# untitled.net
KiCad netlist of a schematic drawn in EAGLE
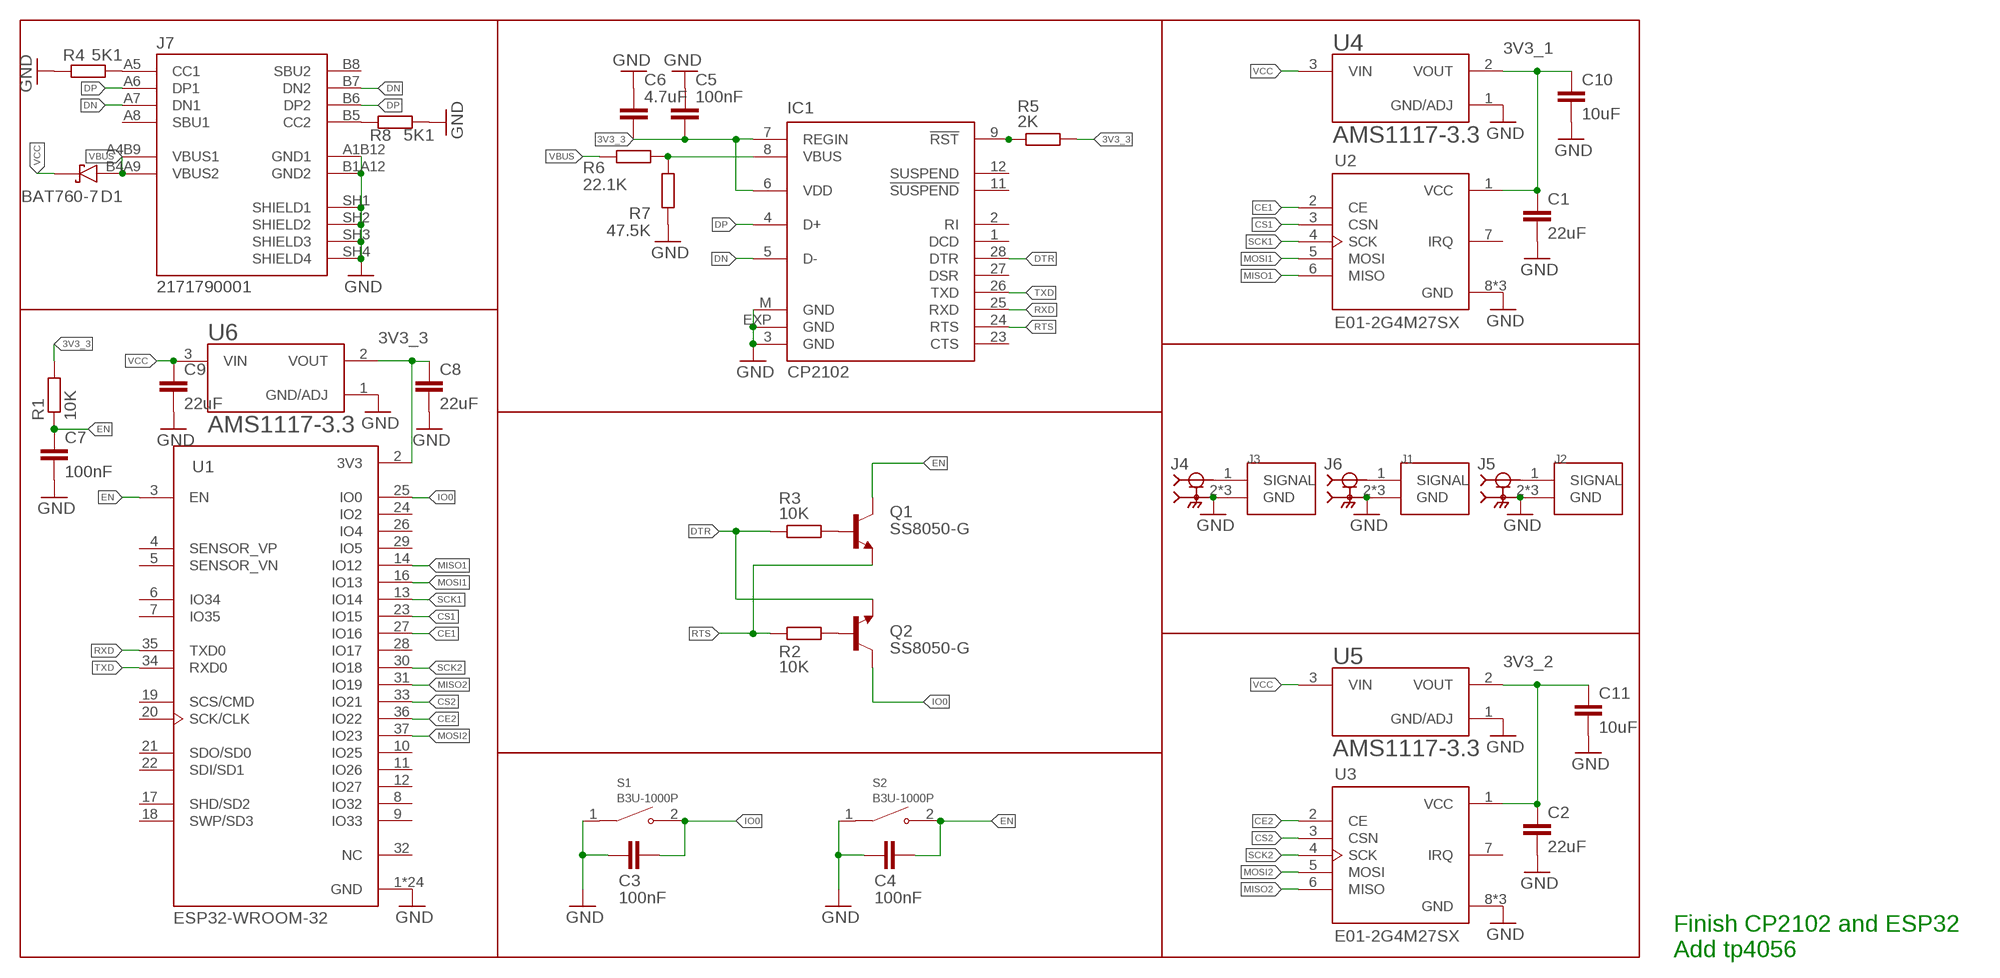
[diagram p0: schematic, sheet 1]

(export (version "E")
  (design (tool "Eeschema 10.0.6"))
  (components
    (comp (ref "C1")
      (value "22uF")
      (footprint "eagle-import:C0603")
      (libsource (lib "eagle-import") (part "C-EUC0603"))
    )
    (comp (ref "C2")
      (value "22uF")
      (footprint "eagle-import:C0603")
      (libsource (lib "eagle-import") (part "C-EUC0603"))
    )
    (comp (ref "C3")
      (value "100nF")
      (footprint "eagle-import:C0603")
      (libsource (lib "eagle-import") (part "C-EUC0603"))
    )
    (comp (ref "C4")
      (value "100nF")
      (footprint "eagle-import:C0603")
      (libsource (lib "eagle-import") (part "C-EUC0603"))
    )
    (comp (ref "C5")
      (value "100nF")
      (footprint "eagle-import:C0603")
      (libsource (lib "eagle-import") (part "C-EUC0603"))
    )
    (comp (ref "C6")
      (value "4.7uF")
      (footprint "eagle-import:C0603")
      (libsource (lib "eagle-import") (part "C-EUC0603"))
    )
    (comp (ref "C7")
      (value "100nF")
      (footprint "eagle-import:C0603")
      (libsource (lib "eagle-import") (part "C-EUC0603"))
    )
    (comp (ref "C8")
      (value "22uF")
      (footprint "eagle-import:C0603")
      (libsource (lib "eagle-import") (part "C-EUC0603"))
    )
    (comp (ref "C9")
      (value "22uF")
      (footprint "eagle-import:C0603")
      (libsource (lib "eagle-import") (part "C-EUC0603"))
    )
    (comp (ref "C10")
      (value "10uF")
      (footprint "eagle-import:C0603")
      (libsource (lib "eagle-import") (part "C-EUC0603"))
    )
    (comp (ref "C11")
      (value "10uF")
      (footprint "eagle-import:C0603")
      (libsource (lib "eagle-import") (part "C-EUC0603"))
    )
    (comp (ref "D1")
      (value "BAT760-7")
      (footprint "eagle-import:SOD2513X120N")
      (fields (field (name "MF") "Diodes Inc."))
      (libsource (lib "eagle-import") (part "BAT760-7"))
    )
    (comp (ref "IC1")
      (value "CP2102")
      (footprint "eagle-import:MLP28")
      (fields (field (name "MF") "FARNELL") (field (name "MPN") "CP2102-GM"))
      (libsource (lib "eagle-import") (part "CP2102"))
    )
    (comp (ref "J1")
      (value "RSP-122811-02")
      (footprint "eagle-import:SAMTEC_RSP-122811-02")
      (fields (field (name "MF") "Samtec Inc."))
      (libsource (lib "eagle-import") (part "RSP-122811-02"))
    )
    (comp (ref "J2")
      (value "RSP-122811-02")
      (footprint "eagle-import:SAMTEC_RSP-122811-02")
      (fields (field (name "MF") "Samtec Inc."))
      (libsource (lib "eagle-import") (part "RSP-122811-02"))
    )
    (comp (ref "J3")
      (value "RSP-122811-02")
      (footprint "eagle-import:SAMTEC_RSP-122811-02")
      (fields (field (name "MF") "Samtec Inc."))
      (libsource (lib "eagle-import") (part "RSP-122811-02"))
    )
    (comp (ref "J4")
      (value "SMA-J-P-X-RA-TH1")
      (footprint "eagle-import:SAMTEC_SMA-J-P-X-RA-TH1")
      (fields (field (name "MF") "Samtec") (field (name "MP") "SMA-J-P-H-RA-TH1"))
      (libsource (lib "eagle-import") (part "SMA-J-P-X-RA-TH1"))
    )
    (comp (ref "J5")
      (value "SMA-J-P-X-RA-TH1")
      (footprint "eagle-import:SAMTEC_SMA-J-P-X-RA-TH1")
      (fields (field (name "MF") "Samtec") (field (name "MP") "SMA-J-P-H-RA-TH1"))
      (libsource (lib "eagle-import") (part "SMA-J-P-X-RA-TH1"))
    )
    (comp (ref "J6")
      (value "SMA-J-P-X-RA-TH1")
      (footprint "eagle-import:SAMTEC_SMA-J-P-X-RA-TH1")
      (fields (field (name "MF") "Samtec") (field (name "MP") "SMA-J-P-H-RA-TH1"))
      (libsource (lib "eagle-import") (part "SMA-J-P-X-RA-TH1"))
    )
    (comp (ref "J7")
      (value "2171790001")
      (footprint "eagle-import:MOLEX_2171790001")
      (fields (field (name "MF") "Molex") (field (name "MP") "217179-0001"))
      (libsource (lib "eagle-import") (part "2171790001"))
    )
    (comp (ref "Q1")
      (value "SS8050-G")
      (footprint "eagle-import:TRANS_SS8050-G")
      (fields (field (name "MF") "Comchip Technology"))
      (libsource (lib "eagle-import") (part "SS8050-G"))
    )
    (comp (ref "Q2")
      (value "SS8050-G")
      (footprint "eagle-import:TRANS_SS8050-G")
      (fields (field (name "MF") "Comchip Technology"))
      (libsource (lib "eagle-import") (part "SS8050-G"))
    )
    (comp (ref "R1")
      (value "10K")
      (footprint "eagle-import:R0603")
      (libsource (lib "eagle-import") (part "R-EU_R0603"))
    )
    (comp (ref "R2")
      (value "10K")
      (footprint "eagle-import:R0603")
      (libsource (lib "eagle-import") (part "R-EU_R0603"))
    )
    (comp (ref "R3")
      (value "10K")
      (footprint "eagle-import:R0603")
      (libsource (lib "eagle-import") (part "R-EU_R0603"))
    )
    (comp (ref "R4")
      (value "5K1")
      (footprint "eagle-import:R0603")
      (libsource (lib "eagle-import") (part "R-EU_R0603"))
    )
    (comp (ref "R5")
      (value "2K")
      (footprint "eagle-import:R0603")
      (libsource (lib "eagle-import") (part "R-EU_R0603"))
    )
    (comp (ref "R6")
      (value "22.1K")
      (footprint "eagle-import:R0603")
      (libsource (lib "eagle-import") (part "R-EU_R0603"))
    )
    (comp (ref "R7")
      (value "47.5K")
      (footprint "eagle-import:R0603")
      (libsource (lib "eagle-import") (part "R-EU_R0603"))
    )
    (comp (ref "R8")
      (value "5K1")
      (footprint "eagle-import:R0603")
      (libsource (lib "eagle-import") (part "R-EU_R0603"))
    )
    (comp (ref "S1")
      (value "B3U-1000P")
      (footprint "eagle-import:SW_B3U-1000P")
      (fields (field (name "MF") "Omron"))
      (libsource (lib "eagle-import") (part "B3U-1000P"))
    )
    (comp (ref "S2")
      (value "B3U-1000P")
      (footprint "eagle-import:SW_B3U-1000P")
      (fields (field (name "MF") "Omron"))
      (libsource (lib "eagle-import") (part "B3U-1000P"))
    )
    (comp (ref "U1")
      (value "ESP32-WROOM-32")
      (footprint "eagle-import:MODULE_ESP32-WROOM-32")
      (fields (field (name "MF") "Espressif Systems"))
      (libsource (lib "eagle-import") (part "ESP32-WROOM-32"))
    )
    (comp (ref "U2")
      (value "E01-2G4M27SX")
      (footprint "eagle-import:XCVR_E01-2G4M27SX")
      (fields (field (name "MF") "EBYTE"))
      (libsource (lib "eagle-import") (part "E01-2G4M27SX"))
    )
    (comp (ref "U3")
      (value "E01-2G4M27SX")
      (footprint "eagle-import:XCVR_E01-2G4M27SX")
      (fields (field (name "MF") "EBYTE"))
      (libsource (lib "eagle-import") (part "E01-2G4M27SX"))
    )
    (comp (ref "U4")
      (value "AMS1117-3.3")
      (footprint "eagle-import:SOT229P700X180-4N")
      (fields (field (name "MF") "Advanced Monolithic Systems"))
      (libsource (lib "eagle-import") (part "AMS1117-3.3"))
    )
    (comp (ref "U5")
      (value "AMS1117-3.3")
      (footprint "eagle-import:SOT229P700X180-4N")
      (fields (field (name "MF") "Advanced Monolithic Systems"))
      (libsource (lib "eagle-import") (part "AMS1117-3.3"))
    )
    (comp (ref "U6")
      (value "AMS1117-3.3")
      (footprint "eagle-import:SOT229P700X180-4N")
      (fields (field (name "MF") "Advanced Monolithic Systems"))
      (libsource (lib "eagle-import") (part "AMS1117-3.3"))
    )
  )
  (nets
    (net (code "1") (name "/3V3_1") (class "Default")
      (node (ref "C1") (pin "1") (pinfunction "1_1") (pintype "passive"))
      (node (ref "C10") (pin "1") (pinfunction "1_1") (pintype "passive"))
      (node (ref "U2") (pin "1") (pinfunction "VCC_1") (pintype "power_in"))
      (node (ref "U4") (pin "2") (pinfunction "VOUT_2") (pintype "output"))
    )
    (net (code "2") (name "/3V3_2") (class "Default")
      (node (ref "C11") (pin "1") (pinfunction "1_1") (pintype "passive"))
      (node (ref "C2") (pin "1") (pinfunction "1_1") (pintype "passive"))
      (node (ref "U3") (pin "1") (pinfunction "VCC_1") (pintype "power_in"))
      (node (ref "U5") (pin "2") (pinfunction "VOUT_2") (pintype "output"))
    )
    (net (code "3") (name "3V3_3") (class "Default")
      (node (ref "C5") (pin "2") (pinfunction "2_2") (pintype "passive"))
      (node (ref "C6") (pin "2") (pinfunction "2_2") (pintype "passive"))
      (node (ref "C8") (pin "1") (pinfunction "1_1") (pintype "passive"))
      (node (ref "IC1") (pin "6") (pinfunction "VDD_6") (pintype "power_in"))
      (node (ref "IC1") (pin "7") (pinfunction "REGIN_7") (pintype "passive"))
      (node (ref "R1") (pin "2") (pinfunction "2_2") (pintype "passive"))
      (node (ref "R5") (pin "2") (pinfunction "2_2") (pintype "passive"))
      (node (ref "U1") (pin "2") (pinfunction "3V3_2") (pintype "power_in"))
      (node (ref "U6") (pin "2") (pinfunction "VOUT_2") (pintype "output"))
    )
    (net (code "4") (name "CE1") (class "Default")
      (node (ref "U1") (pin "27") (pinfunction "IO16_27") (pintype "bidirectional"))
      (node (ref "U2") (pin "2") (pinfunction "CE_2") (pintype "input"))
    )
    (net (code "5") (name "CE2") (class "Default")
      (node (ref "U1") (pin "36") (pinfunction "IO22_36") (pintype "bidirectional"))
      (node (ref "U3") (pin "2") (pinfunction "CE_2") (pintype "input"))
    )
    (net (code "6") (name "CS1") (class "Default")
      (node (ref "U1") (pin "23") (pinfunction "IO15_23") (pintype "bidirectional"))
      (node (ref "U2") (pin "3") (pinfunction "CSN_3") (pintype "input"))
    )
    (net (code "7") (name "CS2") (class "Default")
      (node (ref "U1") (pin "33") (pinfunction "IO21_33") (pintype "bidirectional"))
      (node (ref "U3") (pin "3") (pinfunction "CSN_3") (pintype "input"))
    )
    (net (code "8") (name "DN") (class "Default")
      (node (ref "IC1") (pin "5") (pinfunction "D-_5") (pintype "bidirectional"))
      (node (ref "J7") (pin "A7") (pinfunction "DN1_A7") (pintype "bidirectional"))
      (node (ref "J7") (pin "B7") (pinfunction "DN2_B7") (pintype "bidirectional"))
    )
    (net (code "9") (name "DP") (class "Default")
      (node (ref "IC1") (pin "4") (pinfunction "D+_4") (pintype "bidirectional"))
      (node (ref "J7") (pin "A6") (pinfunction "DP1_A6") (pintype "bidirectional"))
      (node (ref "J7") (pin "B6") (pinfunction "DP2_B6") (pintype "bidirectional"))
    )
    (net (code "10") (name "DTR") (class "Default")
      (node (ref "IC1") (pin "28") (pinfunction "DTR_28") (pintype "output"))
      (node (ref "Q2") (pin "2") (pinfunction "E_2") (pintype "passive"))
      (node (ref "R3") (pin "1") (pinfunction "1_1") (pintype "passive"))
    )
    (net (code "11") (name "EN") (class "Default")
      (node (ref "C4") (pin "2") (pinfunction "2_2") (pintype "passive"))
      (node (ref "C7") (pin "1") (pinfunction "1_1") (pintype "passive"))
      (node (ref "Q1") (pin "3") (pinfunction "C_3") (pintype "passive"))
      (node (ref "R1") (pin "1") (pinfunction "1_1") (pintype "passive"))
      (node (ref "S2") (pin "2") (pinfunction "2_2") (pintype "passive"))
      (node (ref "U1") (pin "3") (pinfunction "EN_3") (pintype "input"))
    )
    (net (code "12") (name "GND") (class "Default")
      (node (ref "C1") (pin "2") (pinfunction "2_2") (pintype "passive"))
      (node (ref "C10") (pin "2") (pinfunction "2_2") (pintype "passive"))
      (node (ref "C11") (pin "2") (pinfunction "2_2") (pintype "passive"))
      (node (ref "C2") (pin "2") (pinfunction "2_2") (pintype "passive"))
      (node (ref "C3") (pin "1") (pinfunction "1_1") (pintype "passive"))
      (node (ref "C4") (pin "1") (pinfunction "1_1") (pintype "passive"))
      (node (ref "C5") (pin "1") (pinfunction "1_1") (pintype "passive"))
      (node (ref "C6") (pin "1") (pinfunction "1_1") (pintype "passive"))
      (node (ref "C7") (pin "2") (pinfunction "2_2") (pintype "passive"))
      (node (ref "C8") (pin "2") (pinfunction "2_2") (pintype "passive"))
      (node (ref "C9") (pin "2") (pinfunction "2_2") (pintype "passive"))
      (node (ref "IC1") (pin "3") (pinfunction "GND_3") (pintype "power_in"))
      (node (ref "IC1") (pin "EXP") (pinfunction "GND_EXP") (pintype "power_in"))
      (node (ref "IC1") (pin "M") (pinfunction "GND_M") (pintype "power_in"))
      (node (ref "J1") (pin "2") (pinfunction "GND_2") (pintype "power_in"))
      (node (ref "J1") (pin "3") (pinfunction "GND_3") (pintype "power_in"))
      (node (ref "J1") (pin "4") (pinfunction "GND_4") (pintype "power_in"))
      (node (ref "J2") (pin "2") (pinfunction "GND_2") (pintype "power_in"))
      (node (ref "J2") (pin "3") (pinfunction "GND_3") (pintype "power_in"))
      (node (ref "J2") (pin "4") (pinfunction "GND_4") (pintype "power_in"))
      (node (ref "J3") (pin "2") (pinfunction "GND_2") (pintype "power_in"))
      (node (ref "J3") (pin "3") (pinfunction "GND_3") (pintype "power_in"))
      (node (ref "J3") (pin "4") (pinfunction "GND_4") (pintype "power_in"))
      (node (ref "J4") (pin "2") (pinfunction "2_2") (pintype "passive"))
      (node (ref "J4") (pin "3") (pinfunction "2_3") (pintype "passive"))
      (node (ref "J4") (pin "4") (pinfunction "2_4") (pintype "passive"))
      (node (ref "J4") (pin "5") (pinfunction "2_5") (pintype "passive"))
      (node (ref "J5") (pin "2") (pinfunction "2_2") (pintype "passive"))
      (node (ref "J5") (pin "3") (pinfunction "2_3") (pintype "passive"))
      (node (ref "J5") (pin "4") (pinfunction "2_4") (pintype "passive"))
      (node (ref "J5") (pin "5") (pinfunction "2_5") (pintype "passive"))
      (node (ref "J6") (pin "2") (pinfunction "2_2") (pintype "passive"))
      (node (ref "J6") (pin "3") (pinfunction "2_3") (pintype "passive"))
      (node (ref "J6") (pin "4") (pinfunction "2_4") (pintype "passive"))
      (node (ref "J6") (pin "5") (pinfunction "2_5") (pintype "passive"))
      (node (ref "J7") (pin "A1B12") (pinfunction "GND1_A1B12") (pintype "power_in"))
      (node (ref "J7") (pin "B1A12") (pinfunction "GND2_B1A12") (pintype "power_in"))
      (node (ref "J7") (pin "SH1") (pinfunction "SHIELD1_SH1") (pintype "passive"))
      (node (ref "J7") (pin "SH2") (pinfunction "SHIELD2_SH2") (pintype "passive"))
      (node (ref "J7") (pin "SH3") (pinfunction "SHIELD3_SH3") (pintype "passive"))
      (node (ref "J7") (pin "SH4") (pinfunction "SHIELD4_SH4") (pintype "passive"))
      (node (ref "R4") (pin "1") (pinfunction "1_1") (pintype "passive"))
      (node (ref "R7") (pin "1") (pinfunction "1_1") (pintype "passive"))
      (node (ref "R8") (pin "2") (pinfunction "2_2") (pintype "passive"))
      (node (ref "S1") (pin "1") (pinfunction "1_1") (pintype "passive"))
      (node (ref "S2") (pin "1") (pinfunction "1_1") (pintype "passive"))
      (node (ref "U1") (pin "1") (pinfunction "GND_1") (pintype "power_in"))
      (node (ref "U1") (pin "15") (pinfunction "GND_15") (pintype "power_in"))
      (node (ref "U1") (pin "38") (pinfunction "GND_38") (pintype "power_in"))
      (node (ref "U1") (pin "39_1") (pinfunction "GND_39_1") (pintype "power_in"))
      (node (ref "U1") (pin "39_10") (pinfunction "GND_39_10") (pintype "power_in"))
      (node (ref "U1") (pin "39_11") (pinfunction "GND_39_11") (pintype "power_in"))
      (node (ref "U1") (pin "39_12") (pinfunction "GND_39_12") (pintype "power_in"))
      (node (ref "U1") (pin "39_13") (pinfunction "GND_39_13") (pintype "power_in"))
      (node (ref "U1") (pin "39_14") (pinfunction "GND_39_14") (pintype "power_in"))
      (node (ref "U1") (pin "39_15") (pinfunction "GND_39_15") (pintype "power_in"))
      (node (ref "U1") (pin "39_16") (pinfunction "GND_39_16") (pintype "power_in"))
      (node (ref "U1") (pin "39_17") (pinfunction "GND_39_17") (pintype "power_in"))
      (node (ref "U1") (pin "39_18") (pinfunction "GND_39_18") (pintype "power_in"))
      (node (ref "U1") (pin "39_19") (pinfunction "GND_39_19") (pintype "power_in"))
      (node (ref "U1") (pin "39_2") (pinfunction "GND_39_2") (pintype "power_in"))
      (node (ref "U1") (pin "39_20") (pinfunction "GND_39_20") (pintype "power_in"))
      (node (ref "U1") (pin "39_21") (pinfunction "GND_39_21") (pintype "power_in"))
      (node (ref "U1") (pin "39_3") (pinfunction "GND_39_3") (pintype "power_in"))
      (node (ref "U1") (pin "39_4") (pinfunction "GND_39_4") (pintype "power_in"))
      (node (ref "U1") (pin "39_5") (pinfunction "GND_39_5") (pintype "power_in"))
      (node (ref "U1") (pin "39_6") (pinfunction "GND_39_6") (pintype "power_in"))
      (node (ref "U1") (pin "39_7") (pinfunction "GND_39_7") (pintype "power_in"))
      (node (ref "U1") (pin "39_8") (pinfunction "GND_39_8") (pintype "power_in"))
      (node (ref "U1") (pin "39_9") (pinfunction "GND_39_9") (pintype "power_in"))
      (node (ref "U2") (pin "10") (pinfunction "GND_10") (pintype "power_in"))
      (node (ref "U2") (pin "8") (pinfunction "GND_8") (pintype "power_in"))
      (node (ref "U2") (pin "9") (pinfunction "GND_9") (pintype "power_in"))
      (node (ref "U3") (pin "10") (pinfunction "GND_10") (pintype "power_in"))
      (node (ref "U3") (pin "8") (pinfunction "GND_8") (pintype "power_in"))
      (node (ref "U3") (pin "9") (pinfunction "GND_9") (pintype "power_in"))
      (node (ref "U4") (pin "1") (pinfunction "GND/ADJ_1") (pintype "power_in"))
      (node (ref "U5") (pin "1") (pinfunction "GND/ADJ_1") (pintype "power_in"))
      (node (ref "U6") (pin "1") (pinfunction "GND/ADJ_1") (pintype "power_in"))
    )
    (net (code "13") (name "IO0") (class "Default")
      (node (ref "C3") (pin "2") (pinfunction "2_2") (pintype "passive"))
      (node (ref "Q2") (pin "3") (pinfunction "C_3") (pintype "passive"))
      (node (ref "S1") (pin "2") (pinfunction "2_2") (pintype "passive"))
      (node (ref "U1") (pin "25") (pinfunction "IO0_25") (pintype "bidirectional"))
    )
    (net (code "14") (name "MISO1") (class "Default")
      (node (ref "U1") (pin "14") (pinfunction "IO12_14") (pintype "bidirectional"))
      (node (ref "U2") (pin "6") (pinfunction "MISO_6") (pintype "output"))
    )
    (net (code "15") (name "MISO2") (class "Default")
      (node (ref "U1") (pin "31") (pinfunction "IO19_31") (pintype "bidirectional"))
      (node (ref "U3") (pin "6") (pinfunction "MISO_6") (pintype "output"))
    )
    (net (code "16") (name "MOSI1") (class "Default")
      (node (ref "U1") (pin "16") (pinfunction "IO13_16") (pintype "bidirectional"))
      (node (ref "U2") (pin "5") (pinfunction "MOSI_5") (pintype "input"))
    )
    (net (code "17") (name "MOSI2") (class "Default")
      (node (ref "U1") (pin "37") (pinfunction "IO23_37") (pintype "bidirectional"))
      (node (ref "U3") (pin "5") (pinfunction "MOSI_5") (pintype "input"))
    )
    (net (code "18") (name "Net-(IC1-VBUS)") (class "Default")
      (node (ref "IC1") (pin "8") (pinfunction "VBUS_8") (pintype "input"))
      (node (ref "R6") (pin "2") (pinfunction "2_2") (pintype "passive"))
      (node (ref "R7") (pin "2") (pinfunction "2_2") (pintype "passive"))
    )
    (net (code "19") (name "Net-(IC1-~{RST})") (class "Default")
      (node (ref "IC1") (pin "9") (pinfunction "~{RST}_9") (pintype "bidirectional"))
      (node (ref "R5") (pin "1") (pinfunction "1_1") (pintype "passive"))
    )
    (net (code "20") (name "Net-(J1-SIGNAL)") (class "Default")
      (node (ref "J1") (pin "1") (pinfunction "SIGNAL_1") (pintype "power_in"))
      (node (ref "J6") (pin "1") (pinfunction "1_1") (pintype "passive"))
    )
    (net (code "21") (name "Net-(J2-SIGNAL)") (class "Default")
      (node (ref "J2") (pin "1") (pinfunction "SIGNAL_1") (pintype "power_in"))
      (node (ref "J5") (pin "1") (pinfunction "1_1") (pintype "passive"))
    )
    (net (code "22") (name "Net-(J3-SIGNAL)") (class "Default")
      (node (ref "J3") (pin "1") (pinfunction "SIGNAL_1") (pintype "power_in"))
      (node (ref "J4") (pin "1") (pinfunction "1_1") (pintype "passive"))
    )
    (net (code "23") (name "Net-(J7-CC1)") (class "Default")
      (node (ref "J7") (pin "A5") (pinfunction "CC1_A5") (pintype "bidirectional"))
      (node (ref "R4") (pin "2") (pinfunction "2_2") (pintype "passive"))
    )
    (net (code "24") (name "Net-(J7-CC2)") (class "Default")
      (node (ref "J7") (pin "B5") (pinfunction "CC2_B5") (pintype "bidirectional"))
      (node (ref "R8") (pin "1") (pinfunction "1_1") (pintype "passive"))
    )
    (net (code "25") (name "Net-(Q1-B)") (class "Default")
      (node (ref "Q1") (pin "1") (pinfunction "B_1") (pintype "passive"))
      (node (ref "R3") (pin "2") (pinfunction "2_2") (pintype "passive"))
    )
    (net (code "26") (name "Net-(Q2-B)") (class "Default")
      (node (ref "Q2") (pin "1") (pinfunction "B_1") (pintype "passive"))
      (node (ref "R2") (pin "2") (pinfunction "2_2") (pintype "passive"))
    )
    (net (code "27") (name "RTS") (class "Default")
      (node (ref "IC1") (pin "24") (pinfunction "RTS_24") (pintype "output"))
      (node (ref "Q1") (pin "2") (pinfunction "E_2") (pintype "passive"))
      (node (ref "R2") (pin "1") (pinfunction "1_1") (pintype "passive"))
    )
    (net (code "28") (name "RXD") (class "Default")
      (node (ref "IC1") (pin "25") (pinfunction "RXD_25") (pintype "input"))
      (node (ref "U1") (pin "35") (pinfunction "TXD0_35") (pintype "bidirectional"))
    )
    (net (code "29") (name "SCK1") (class "Default")
      (node (ref "U1") (pin "13") (pinfunction "IO14_13") (pintype "bidirectional"))
      (node (ref "U2") (pin "4") (pinfunction "SCK_4") (pintype "input"))
    )
    (net (code "30") (name "SCK2") (class "Default")
      (node (ref "U1") (pin "30") (pinfunction "IO18_30") (pintype "bidirectional"))
      (node (ref "U3") (pin "4") (pinfunction "SCK_4") (pintype "input"))
    )
    (net (code "31") (name "TXD") (class "Default")
      (node (ref "IC1") (pin "26") (pinfunction "TXD_26") (pintype "output"))
      (node (ref "U1") (pin "34") (pinfunction "RXD0_34") (pintype "bidirectional"))
    )
    (net (code "32") (name "VBUS") (class "Default")
      (node (ref "D1") (pin "A") (pinfunction "A_A") (pintype "passive"))
      (node (ref "J7") (pin "A4B9") (pinfunction "VBUS1_A4B9") (pintype "power_in"))
      (node (ref "J7") (pin "B4A9") (pinfunction "VBUS2_B4A9") (pintype "power_in"))
      (node (ref "R6") (pin "1") (pinfunction "1_1") (pintype "passive"))
    )
    (net (code "33") (name "VCC") (class "Default")
      (node (ref "C9") (pin "1") (pinfunction "1_1") (pintype "passive"))
      (node (ref "D1") (pin "C") (pinfunction "K_C") (pintype "passive"))
      (node (ref "U4") (pin "3") (pinfunction "VIN_3") (pintype "input"))
      (node (ref "U5") (pin "3") (pinfunction "VIN_3") (pintype "input"))
      (node (ref "U6") (pin "3") (pinfunction "VIN_3") (pintype "input"))
    )
    (net (code "34") (name "unconnected-(IC1-CTS-Pad23)") (class "Default")
      (node (ref "IC1") (pin "23") (pinfunction "CTS_23") (pintype "input"))
    )
    (net (code "35") (name "unconnected-(IC1-DCD-Pad1)") (class "Default")
      (node (ref "IC1") (pin "1") (pinfunction "DCD_1") (pintype "input"))
    )
    (net (code "36") (name "unconnected-(IC1-DSR-Pad27)") (class "Default")
      (node (ref "IC1") (pin "27") (pinfunction "DSR_27") (pintype "input"))
    )
    (net (code "37") (name "unconnected-(IC1-RI-Pad2)") (class "Default")
      (node (ref "IC1") (pin "2") (pinfunction "RI_2") (pintype "input"))
    )
    (net (code "38") (name "unconnected-(IC1-SUSPEND-Pad12)") (class "Default")
      (node (ref "IC1") (pin "12") (pinfunction "SUSPEND_12") (pintype "output"))
    )
    (net (code "39") (name "unconnected-(IC1-~{SUSPEND}-Pad11)") (class "Default")
      (node (ref "IC1") (pin "11") (pinfunction "~{SUSPEND}_11") (pintype "output"))
    )
    (net (code "40") (name "unconnected-(J7-SBU1-PadA8)") (class "Default")
      (node (ref "J7") (pin "A8") (pinfunction "SBU1_A8") (pintype "bidirectional"))
    )
    (net (code "41") (name "unconnected-(J7-SBU2-PadB8)") (class "Default")
      (node (ref "J7") (pin "B8") (pinfunction "SBU2_B8") (pintype "bidirectional"))
    )
    (net (code "42") (name "unconnected-(U1-IO2-Pad24)") (class "Default")
      (node (ref "U1") (pin "24") (pinfunction "IO2_24") (pintype "bidirectional"))
    )
    (net (code "43") (name "unconnected-(U1-IO4-Pad26)") (class "Default")
      (node (ref "U1") (pin "26") (pinfunction "IO4_26") (pintype "bidirectional"))
    )
    (net (code "44") (name "unconnected-(U1-IO5-Pad29)") (class "Default")
      (node (ref "U1") (pin "29") (pinfunction "IO5_29") (pintype "bidirectional"))
    )
    (net (code "45") (name "unconnected-(U1-IO17-Pad28)") (class "Default")
      (node (ref "U1") (pin "28") (pinfunction "IO17_28") (pintype "bidirectional"))
    )
    (net (code "46") (name "unconnected-(U1-IO25-Pad10)") (class "Default")
      (node (ref "U1") (pin "10") (pinfunction "IO25_10") (pintype "bidirectional"))
    )
    (net (code "47") (name "unconnected-(U1-IO26-Pad11)") (class "Default")
      (node (ref "U1") (pin "11") (pinfunction "IO26_11") (pintype "bidirectional"))
    )
    (net (code "48") (name "unconnected-(U1-IO27-Pad12)") (class "Default")
      (node (ref "U1") (pin "12") (pinfunction "IO27_12") (pintype "bidirectional"))
    )
    (net (code "49") (name "unconnected-(U1-IO32-Pad8)") (class "Default")
      (node (ref "U1") (pin "8") (pinfunction "IO32_8") (pintype "bidirectional"))
    )
    (net (code "50") (name "unconnected-(U1-IO33-Pad9)") (class "Default")
      (node (ref "U1") (pin "9") (pinfunction "IO33_9") (pintype "bidirectional"))
    )
    (net (code "51") (name "unconnected-(U1-IO34-Pad6)") (class "Default")
      (node (ref "U1") (pin "6") (pinfunction "IO34_6") (pintype "input"))
    )
    (net (code "52") (name "unconnected-(U1-IO35-Pad7)") (class "Default")
      (node (ref "U1") (pin "7") (pinfunction "IO35_7") (pintype "input"))
    )
    (net (code "53") (name "unconnected-(U1-NC-Pad32)") (class "Default")
      (node (ref "U1") (pin "32") (pinfunction "NC_32") (pintype "no_connect"))
    )
    (net (code "54") (name "unconnected-(U1-SCK{slash}CLK-Pad20)") (class "Default")
      (node (ref "U1") (pin "20") (pinfunction "SCK/CLK_20") (pintype "bidirectional"))
    )
    (net (code "55") (name "unconnected-(U1-SCS{slash}CMD-Pad19)") (class "Default")
      (node (ref "U1") (pin "19") (pinfunction "SCS/CMD_19") (pintype "bidirectional"))
    )
    (net (code "56") (name "unconnected-(U1-SDI{slash}SD1-Pad22)") (class "Default")
      (node (ref "U1") (pin "22") (pinfunction "SDI/SD1_22") (pintype "bidirectional"))
    )
    (net (code "57") (name "unconnected-(U1-SDO{slash}SD0-Pad21)") (class "Default")
      (node (ref "U1") (pin "21") (pinfunction "SDO/SD0_21") (pintype "bidirectional"))
    )
    (net (code "58") (name "unconnected-(U1-SENSOR_VN-Pad5)") (class "Default")
      (node (ref "U1") (pin "5") (pinfunction "SENSOR_VN_5") (pintype "input"))
    )
    (net (code "59") (name "unconnected-(U1-SENSOR_VP-Pad4)") (class "Default")
      (node (ref "U1") (pin "4") (pinfunction "SENSOR_VP_4") (pintype "input"))
    )
    (net (code "60") (name "unconnected-(U1-SHD{slash}SD2-Pad17)") (class "Default")
      (node (ref "U1") (pin "17") (pinfunction "SHD/SD2_17") (pintype "bidirectional"))
    )
    (net (code "61") (name "unconnected-(U1-SWP{slash}SD3-Pad18)") (class "Default")
      (node (ref "U1") (pin "18") (pinfunction "SWP/SD3_18") (pintype "bidirectional"))
    )
    (net (code "62") (name "unconnected-(U2-IRQ-Pad7)") (class "Default")
      (node (ref "U2") (pin "7") (pinfunction "IRQ_7") (pintype "output"))
    )
    (net (code "63") (name "unconnected-(U3-IRQ-Pad7)") (class "Default")
      (node (ref "U3") (pin "7") (pinfunction "IRQ_7") (pintype "output"))
    )
  )
)
